# Power_Supply.net
KiCad netlist of a schematic drawn in Altium Designer
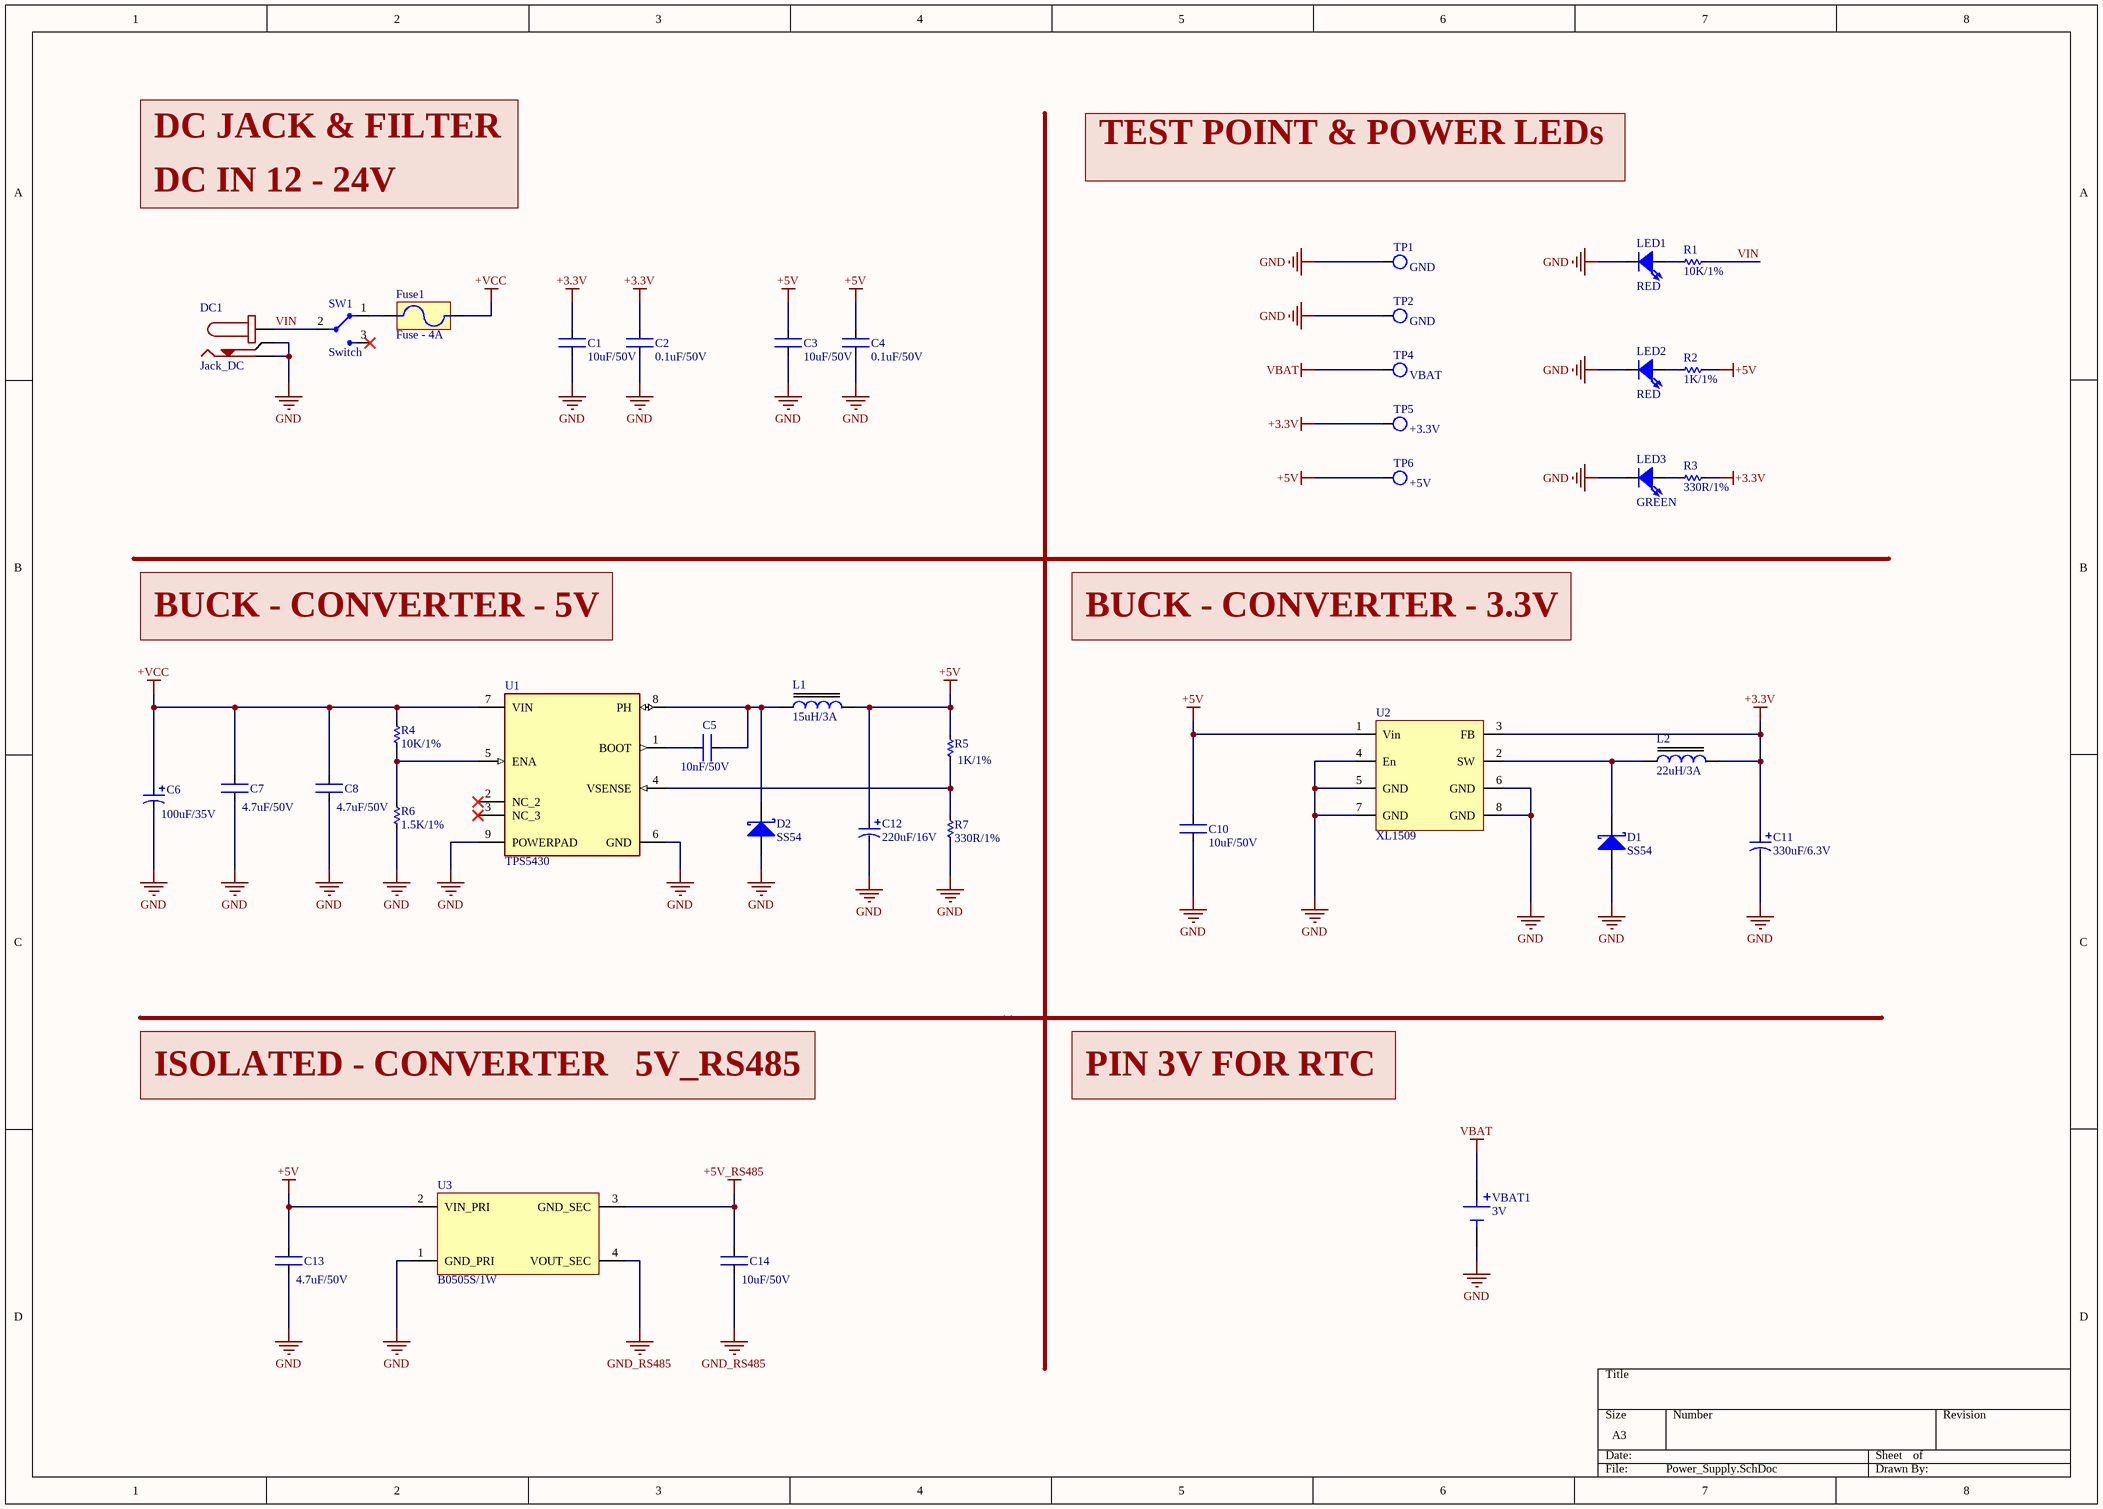
[diagram p0: Power_Supply.SchDoc]

(export (version "E")
  (design (tool "Eeschema 10.0.6"))
  (components
    (comp (ref "C1")
      (value "10uF/50V")
      (footprint "CAP - 0603")
      (description "CAPACITOR SMD - KEMET")
      (libsource (lib "NewLibrary") (part "CAPACITOR"))
    )
    (comp (ref "C2")
      (value "0.1uF/50V")
      (footprint "CAP - 0603")
      (description "CAPACITOR SMD - KEMET")
      (libsource (lib "NewLibrary") (part "CAPACITOR"))
    )
    (comp (ref "C3")
      (value "10uF/50V")
      (footprint "CAP - 0603")
      (description "CAPACITOR SMD - KEMET")
      (libsource (lib "NewLibrary") (part "CAPACITOR"))
    )
    (comp (ref "C4")
      (value "0.1uF/50V")
      (footprint "CAP - 0603")
      (description "CAPACITOR SMD - KEMET")
      (libsource (lib "NewLibrary") (part "CAPACITOR"))
    )
    (comp (ref "C5")
      (value "10nF/50V")
      (footprint "CAP - 0603")
      (description "CAPACITOR SMD - KEMET")
      (libsource (lib "NewLibrary") (part "CAPACITOR"))
    )
    (comp (ref "C6")
      (value "100uF/35V")
      (footprint "Alu_Cap_6.3_7.7")
      (libsource (lib "NewLibrary") (part "Alu_Capacitor"))
    )
    (comp (ref "C7")
      (value "4.7uF/50V")
      (footprint "CAP - 0603")
      (description "CAPACITOR SMD - KEMET")
      (libsource (lib "NewLibrary") (part "CAPACITOR"))
    )
    (comp (ref "C8")
      (value "4.7uF/50V")
      (footprint "CAP - 0603")
      (description "CAPACITOR SMD - KEMET")
      (libsource (lib "NewLibrary") (part "CAPACITOR"))
    )
    (comp (ref "C10")
      (value "10uF/50V")
      (footprint "CAP - 0603")
      (description "CAPACITOR SMD - KEMET")
      (libsource (lib "NewLibrary") (part "CAPACITOR"))
    )
    (comp (ref "C11")
      (value "330uF/6.3V")
      (footprint "Alu_Cap_6.3_7.7")
      (libsource (lib "NewLibrary") (part "Alu_Capacitor"))
    )
    (comp (ref "C12")
      (value "220uF/16V")
      (footprint "Alu_Cap_6.3_7.7")
      (libsource (lib "NewLibrary") (part "Alu_Capacitor"))
    )
    (comp (ref "C13")
      (value "4.7uF/50V")
      (footprint "CAP - 0603")
      (description "CAPACITOR SMD - KEMET")
      (libsource (lib "NewLibrary") (part "CAPACITOR"))
    )
    (comp (ref "C14")
      (value "10uF/50V")
      (footprint "CAP - 0603")
      (description "CAPACITOR SMD - KEMET")
      (libsource (lib "NewLibrary") (part "CAPACITOR"))
    )
    (comp (ref "D1")
      (value "SS54")
      (footprint "SS54")
      (description "DIODE SCHOTTKY 40V 5A SMA")
      (libsource (lib "NewLibrary") (part "SS54"))
    )
    (comp (ref "D2")
      (value "SS54")
      (footprint "SS54")
      (description "DIODE SCHOTTKY 40V 5A SMA")
      (libsource (lib "NewLibrary") (part "SS54"))
    )
    (comp (ref "DC1")
      (value "Jack_DC")
      (footprint "DC_5.5 x 2.1mm")
      (description "Jack DC IN (Hole)")
      (libsource (lib "NewLibrary") (part "Jack_DC"))
    )
    (comp (ref "Fuse1")
      (value "Fuse - 4A")
      (footprint "SMD-2")
      (description "Nano2 SMD FF submin fuse w/holder, 4A ¦ Littelfuse 0154004.DR")
      (libsource (lib "NewLibrary") (part "Fuse"))
    )
    (comp (ref "L1")
      (value "15uH/3A")
      (footprint "L_SMD_0630")
      (libsource (lib "NewLibrary") (part "Inductor_1_SMD"))
    )
    (comp (ref "L2")
      (value "22uH/3A")
      (footprint "L_SMD_0630")
      (libsource (lib "NewLibrary") (part "Inductor_1_SMD"))
    )
    (comp (ref "LED1")
      (value "RED")
      (footprint "RED_LED_0603")
      (description "LED SMD")
      (libsource (lib "NewLibrary") (part "LED_SMD"))
    )
    (comp (ref "LED2")
      (value "RED")
      (footprint "RED_LED_0603")
      (description "LED SMD")
      (libsource (lib "NewLibrary") (part "LED_SMD"))
    )
    (comp (ref "LED3")
      (value "GREEN")
      (footprint "GREEN_LED_0603")
      (description "LED SMD")
      (libsource (lib "NewLibrary") (part "LED_SMD"))
    )
    (comp (ref "R1")
      (value "10K/1%")
      (footprint "RES - 0603")
      (description "Resistor SMD - YAGEO")
      (libsource (lib "NewLibrary") (part "RESISTOR"))
    )
    (comp (ref "R2")
      (value "1K/1%")
      (footprint "RES - 0603")
      (description "Resistor SMD - YAGEO")
      (libsource (lib "NewLibrary") (part "RESISTOR"))
    )
    (comp (ref "R3")
      (value "330R/1%")
      (footprint "RES - 0603")
      (description "Resistor SMD - YAGEO")
      (libsource (lib "NewLibrary") (part "RESISTOR"))
    )
    (comp (ref "R4")
      (value "10K/1%")
      (footprint "RES - 0603")
      (description "Resistor SMD - YAGEO")
      (libsource (lib "NewLibrary") (part "RESISTOR"))
    )
    (comp (ref "R5")
      (value "1K/1%")
      (footprint "RES - 0603")
      (description "Resistor SMD - YAGEO")
      (libsource (lib "NewLibrary") (part "RESISTOR"))
    )
    (comp (ref "R6")
      (value "1.5K/1%")
      (footprint "RES - 0603")
      (description "Resistor SMD - YAGEO")
      (libsource (lib "NewLibrary") (part "RESISTOR"))
    )
    (comp (ref "R7")
      (value "330R/1%")
      (footprint "RES - 0603")
      (description "Resistor SMD - YAGEO")
      (libsource (lib "NewLibrary") (part "RESISTOR"))
    )
    (comp (ref "SW1")
      (value "Switch")
      (footprint "Dip_Switch_3_pins_0")
      (description "Switch 3 Pins")
      (libsource (lib "NewLibrary") (part "Switch"))
    )
    (comp (ref "TP1")
      (value "GND")
      (footprint "Test Point")
      (description "Test Point")
      (libsource (lib "NewLibrary") (part "TEST POINT"))
    )
    (comp (ref "TP2")
      (value "GND")
      (footprint "Test Point")
      (description "Test Point")
      (libsource (lib "NewLibrary") (part "TEST POINT"))
    )
    (comp (ref "TP4")
      (value "VBAT")
      (footprint "Test Point")
      (description "Test Point")
      (libsource (lib "NewLibrary") (part "TEST POINT"))
    )
    (comp (ref "TP5")
      (value "+3.3V")
      (footprint "Test Point")
      (description "Test Point")
      (libsource (lib "NewLibrary") (part "TEST POINT"))
    )
    (comp (ref "TP6")
      (value "+5V")
      (footprint "Test Point")
      (description "Test Point")
      (libsource (lib "NewLibrary") (part "TEST POINT"))
    )
    (comp (ref "U1")
      (value "TPS5430")
      (footprint "TPS5430")
      (description "Buck DC to DC Converter")
      (libsource (lib "NewLibrary") (part "TPS5430"))
    )
    (comp (ref "U2")
      (value "XL1509")
      (footprint "SOP_8")
      (description "Buck Converter")
      (libsource (lib "NewLibrary") (part "XL1509"))
    )
    (comp (ref "U3")
      (value "B0505S/1W")
      (footprint "B0505S/1W")
      (description "Isolated - Converter")
      (libsource (lib "NewLibrary") (part "B0505S/1W"))
    )
    (comp (ref "VBAT1")
      (value "3V")
      (footprint "CR2032 - SMD")
      (description "Battery Base CR2032")
      (libsource (lib "NewLibrary") (part "Battery Base"))
    )
  )
  (nets
    (net (code "1") (name "+3.3V") (class "Default")
      (node (ref "C1") (pin "1") (pinfunction "1_1") (pintype "passive"))
      (node (ref "C11") (pin "1") (pinfunction "1_1") (pintype "passive"))
      (node (ref "C2") (pin "1") (pinfunction "1_1") (pintype "passive"))
      (node (ref "L2") (pin "2") (pinfunction "5_2") (pintype "passive"))
      (node (ref "R3") (pin "1") (pinfunction "1_1") (pintype "passive"))
      (node (ref "TP5") (pin "1") (pinfunction "1_1") (pintype "passive"))
      (node (ref "U2") (pin "3") (pinfunction "FB_3") (pintype "passive"))
    )
    (net (code "2") (name "+5V") (class "Default")
      (node (ref "C10") (pin "1") (pinfunction "1_1") (pintype "passive"))
      (node (ref "C12") (pin "1") (pinfunction "1_1") (pintype "passive"))
      (node (ref "C13") (pin "1") (pinfunction "1_1") (pintype "passive"))
      (node (ref "C3") (pin "1") (pinfunction "1_1") (pintype "passive"))
      (node (ref "C4") (pin "1") (pinfunction "1_1") (pintype "passive"))
      (node (ref "L1") (pin "2") (pinfunction "5_2") (pintype "passive"))
      (node (ref "R2") (pin "1") (pinfunction "1_1") (pintype "passive"))
      (node (ref "R5") (pin "1") (pinfunction "1_1") (pintype "passive"))
      (node (ref "TP6") (pin "1") (pinfunction "1_1") (pintype "passive"))
      (node (ref "U2") (pin "1") (pinfunction "Vin_1") (pintype "passive"))
      (node (ref "U3") (pin "2") (pinfunction "VIN_PRI_2") (pintype "passive"))
    )
    (net (code "3") (name "+5V_RS485") (class "Default")
      (node (ref "C14") (pin "1") (pinfunction "1_1") (pintype "passive"))
      (node (ref "U3") (pin "3") (pinfunction "GND_SEC_3") (pintype "passive"))
    )
    (net (code "4") (name "+VCC") (class "Default")
      (node (ref "C6") (pin "1") (pinfunction "1_1") (pintype "passive"))
      (node (ref "C7") (pin "1") (pinfunction "1_1") (pintype "passive"))
      (node (ref "C8") (pin "1") (pinfunction "1_1") (pintype "passive"))
      (node (ref "Fuse1") (pin "2") (pinfunction "2_2") (pintype "passive"))
      (node (ref "R4") (pin "1") (pinfunction "1_1") (pintype "passive"))
      (node (ref "U1") (pin "7") (pinfunction "VIN_7") (pintype "power_in"))
    )
    (net (code "5") (name "/VIN") (class "Default")
      (node (ref "DC1") (pin "1") (pinfunction "S_1") (pintype "power_in"))
      (node (ref "R1") (pin "1") (pinfunction "1_1") (pintype "passive"))
      (node (ref "SW1") (pin "2") (pintype "passive"))
    )
    (net (code "6") (name "GND") (class "Default")
      (node (ref "C1") (pin "2") (pinfunction "2_2") (pintype "passive"))
      (node (ref "C10") (pin "2") (pinfunction "2_2") (pintype "passive"))
      (node (ref "C11") (pin "2") (pinfunction "2_2") (pintype "passive"))
      (node (ref "C12") (pin "2") (pinfunction "2_2") (pintype "passive"))
      (node (ref "C13") (pin "2") (pinfunction "2_2") (pintype "passive"))
      (node (ref "C2") (pin "2") (pinfunction "2_2") (pintype "passive"))
      (node (ref "C3") (pin "2") (pinfunction "2_2") (pintype "passive"))
      (node (ref "C4") (pin "2") (pinfunction "2_2") (pintype "passive"))
      (node (ref "C6") (pin "2") (pinfunction "2_2") (pintype "passive"))
      (node (ref "C7") (pin "2") (pinfunction "2_2") (pintype "passive"))
      (node (ref "C8") (pin "2") (pinfunction "2_2") (pintype "passive"))
      (node (ref "D1") (pin "1") (pinfunction "A_1") (pintype "passive"))
      (node (ref "D2") (pin "1") (pinfunction "A_1") (pintype "passive"))
      (node (ref "DC1") (pin "2") (pinfunction "TN_2") (pintype "passive"))
      (node (ref "DC1") (pin "3") (pinfunction "T_3") (pintype "passive"))
      (node (ref "LED1") (pin "2") (pinfunction "2_2") (pintype "passive"))
      (node (ref "LED2") (pin "2") (pinfunction "2_2") (pintype "passive"))
      (node (ref "LED3") (pin "2") (pinfunction "2_2") (pintype "passive"))
      (node (ref "R6") (pin "2") (pinfunction "2_2") (pintype "passive"))
      (node (ref "R7") (pin "2") (pinfunction "2_2") (pintype "passive"))
      (node (ref "TP1") (pin "1") (pinfunction "1_1") (pintype "passive"))
      (node (ref "TP2") (pin "1") (pinfunction "1_1") (pintype "passive"))
      (node (ref "U1") (pin "6") (pinfunction "GND_6") (pintype "passive"))
      (node (ref "U1") (pin "9") (pinfunction "POWERPAD_9") (pintype "passive"))
      (node (ref "U2") (pin "4") (pinfunction "En_4") (pintype "passive"))
      (node (ref "U2") (pin "5") (pinfunction "GND_5") (pintype "passive"))
      (node (ref "U2") (pin "6") (pinfunction "GND_6") (pintype "passive"))
      (node (ref "U2") (pin "7") (pinfunction "GND_7") (pintype "passive"))
      (node (ref "U2") (pin "8") (pinfunction "GND_8") (pintype "passive"))
      (node (ref "U3") (pin "1") (pinfunction "GND_PRI_1") (pintype "passive"))
      (node (ref "VBAT1") (pin "N") (pinfunction "NEG_N") (pintype "passive"))
    )
    (net (code "7") (name "GND_RS485") (class "Default")
      (node (ref "C14") (pin "2") (pinfunction "2_2") (pintype "passive"))
      (node (ref "U3") (pin "4") (pinfunction "VOUT_SEC_4") (pintype "passive"))
    )
    (net (code "8") (name "Net-(D1-K)") (class "Default")
      (node (ref "D1") (pin "2") (pinfunction "K_2") (pintype "passive"))
      (node (ref "L2") (pin "1") (pinfunction "4_1") (pintype "passive"))
      (node (ref "U2") (pin "2") (pinfunction "SW_2") (pintype "passive"))
    )
    (net (code "9") (name "Net-(D2-K)") (class "Default")
      (node (ref "C5") (pin "2") (pinfunction "2_2") (pintype "passive"))
      (node (ref "D2") (pin "2") (pinfunction "K_2") (pintype "passive"))
      (node (ref "L1") (pin "1") (pinfunction "4_1") (pintype "passive"))
      (node (ref "U1") (pin "8") (pinfunction "PH_8") (pintype "bidirectional"))
    )
    (net (code "10") (name "Net-(Fuse1-Pad1)") (class "Default")
      (node (ref "Fuse1") (pin "1") (pinfunction "1_1") (pintype "passive"))
      (node (ref "SW1") (pin "1") (pintype "passive"))
    )
    (net (code "11") (name "Net-(LED1-Pad1)") (class "Default")
      (node (ref "LED1") (pin "1") (pinfunction "1_1") (pintype "passive"))
      (node (ref "R1") (pin "2") (pinfunction "2_2") (pintype "passive"))
    )
    (net (code "12") (name "Net-(LED2-Pad1)") (class "Default")
      (node (ref "LED2") (pin "1") (pinfunction "1_1") (pintype "passive"))
      (node (ref "R2") (pin "2") (pinfunction "2_2") (pintype "passive"))
    )
    (net (code "13") (name "Net-(LED3-Pad1)") (class "Default")
      (node (ref "LED3") (pin "1") (pinfunction "1_1") (pintype "passive"))
      (node (ref "R3") (pin "2") (pinfunction "2_2") (pintype "passive"))
    )
    (net (code "14") (name "Net-(U1-BOOT)") (class "Default")
      (node (ref "C5") (pin "1") (pinfunction "1_1") (pintype "passive"))
      (node (ref "U1") (pin "1") (pinfunction "BOOT_1") (pintype "output"))
    )
    (net (code "15") (name "Net-(U1-ENA)") (class "Default")
      (node (ref "R4") (pin "2") (pinfunction "2_2") (pintype "passive"))
      (node (ref "R6") (pin "1") (pinfunction "1_1") (pintype "passive"))
      (node (ref "U1") (pin "5") (pinfunction "ENA_5") (pintype "input"))
    )
    (net (code "16") (name "Net-(U1-VSENSE)") (class "Default")
      (node (ref "R5") (pin "2") (pinfunction "2_2") (pintype "passive"))
      (node (ref "R7") (pin "1") (pinfunction "1_1") (pintype "passive"))
      (node (ref "U1") (pin "4") (pinfunction "VSENSE_4") (pintype "input"))
    )
    (net (code "17") (name "VBAT") (class "Default")
      (node (ref "TP4") (pin "1") (pinfunction "1_1") (pintype "passive"))
      (node (ref "VBAT1") (pin "P") (pinfunction "POS_P") (pintype "passive"))
    )
    (net (code "18") (name "unconnected-(SW1-I{slash}O2-Pad3)") (class "Default")
      (node (ref "SW1") (pin "3") (pinfunction "I/O2_3") (pintype "passive+no_connect"))
    )
    (net (code "19") (name "unconnected-(U1-NC_2-Pad2)") (class "Default")
      (node (ref "U1") (pin "2") (pinfunction "NC_2_2") (pintype "passive+no_connect"))
    )
    (net (code "20") (name "unconnected-(U1-NC_3-Pad3)") (class "Default")
      (node (ref "U1") (pin "3") (pinfunction "NC_3_3") (pintype "passive+no_connect"))
    )
  )
)
